# mpc57_clk.net
KiCad netlist of a schematic drawn in Altium Designer
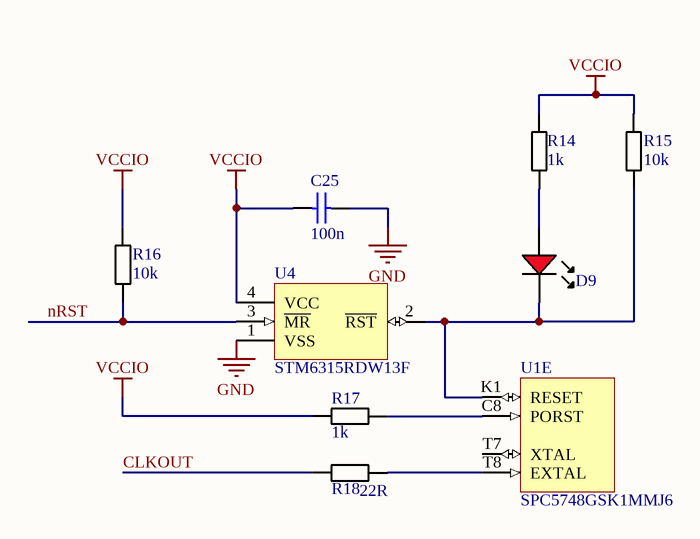
[diagram p0: mpc57_clk.SchDoc]

(export (version "E")
  (design (tool "Eeschema 10.0.6"))
  (components
    (comp (ref "C25")
      (value "100n")
      (footprint "CAPC0402_M")
      (description "100n, 0402")
      (fields (field (name "PART NUMBER") "CCHIP-100n-0402"))
      (libsource (lib "NewAE_AltiumLib") (part "CAP"))
    )
    (comp (ref "D9")
      (value "LED, 0603, Red")
      (footprint "LED-0603-RED")
      (description "Chip LED, Red")
      (fields (field (name "PART NUMBER") "LEDCHIP_0603_RED"))
      (libsource (lib "NewAE_AltiumLib") (part "LED_RED"))
    )
    (comp (ref "R14")
      (value "1k")
      (footprint "RESC1608X55N")
      (description "1k res, 0603, 1%, 1/10W")
      (fields (field (name "PART NUMBER") "RCHIP-1K-0603") (field (name "TOLERANCE") "1%"))
      (libsource (lib "NewAE_AltiumLib") (part "RES-EU"))
    )
    (comp (ref "R15")
      (value "10k")
      (footprint "RESC1608X55N")
      (description "10k res, 0603, 1%, 1/10W")
      (fields (field (name "PART NUMBER") "RCHIP-10K-0603") (field (name "TOLERANCE") "1%"))
      (libsource (lib "NewAE_AltiumLib") (part "RES-EU"))
    )
    (comp (ref "R16")
      (value "10k")
      (footprint "RESC1608X55N")
      (description "10k res, 0603, 1%, 1/10W")
      (fields (field (name "PART NUMBER") "RCHIP-10K-0603") (field (name "TOLERANCE") "1%"))
      (libsource (lib "NewAE_AltiumLib") (part "RES-EU"))
    )
    (comp (ref "R17")
      (value "1k")
      (footprint "RESC1608X55N")
      (description "1k res, 0603, 1%, 1/10W")
      (fields (field (name "PART NUMBER") "RCHIP-1K-0603") (field (name "TOLERANCE") "1%"))
      (libsource (lib "") (part "RES-EU_1"))
    )
    (comp (ref "R18")
      (value "22R")
      (footprint "RESC1608X55N")
      (description "22R res, 0603, 1%, 1/10W")
      (fields (field (name "PART NUMBER") "RCHIP-22R-0603") (field (name "TOLERANCE") "1%"))
      (libsource (lib "") (part "RES-EU_1"))
    )
    (comp (ref "U1")
      (value "SPC5748GSK1MMJ6")
      (footprint "NewAE_AltiumLib:BGA256C100P16X16_1700X1700X170")
      (description "Freescale 32-bit MCU, Triple core, 6MB Flash, 160MHz, -40/+125degC, Automotive Qualified, BGA 256")
      (libsource (lib "NewAE_AltiumLib") (part "SPC5748GSK1MMJ6"))
    )
    (comp (ref "U4")
      (value "STM6315RDW13F")
      (footprint "SOT143B")
      (description "2.93V Reset Controller, 112mS")
      (libsource (lib "NewAE_AltiumLib") (part "STM6315"))
    )
  )
  (nets
    (net (code "1") (name "/CLKOUT") (class "Default")
      (node (ref "R18") (pin "1") (pinfunction "1_1") (pintype "passive"))
    )
    (net (code "2") (name "/nRST") (class "Default")
      (node (ref "R16") (pin "2") (pinfunction "2_2") (pintype "passive"))
      (node (ref "U4") (pin "3") (pinfunction "~{MR}_3") (pintype "input"))
    )
    (net (code "3") (name "GND") (class "Default")
      (node (ref "C25") (pin "2") (pinfunction "2_2") (pintype "passive"))
      (node (ref "U4") (pin "1") (pinfunction "VSS_1") (pintype "power_in"))
    )
    (net (code "4") (name "Net-(D9-PadA)") (class "Default")
      (node (ref "D9") (pin "A") (pinfunction "A_A") (pintype "passive"))
      (node (ref "R14") (pin "2") (pinfunction "2_2") (pintype "passive"))
    )
    (net (code "5") (name "Net-(U1E-EXTAL)") (class "Default")
      (node (ref "R18") (pin "2") (pinfunction "2_2") (pintype "passive"))
      (node (ref "U1") (pin "T8") (pinfunction "EXTAL_T8") (pintype "input"))
    )
    (net (code "6") (name "Net-(U1E-PORST)") (class "Default")
      (node (ref "R17") (pin "2") (pinfunction "2_2") (pintype "passive"))
      (node (ref "U1") (pin "C8") (pinfunction "PORST_C8") (pintype "input"))
    )
    (net (code "7") (name "Net-(U1E-RESET)") (class "Default")
      (node (ref "D9") (pin "K") (pinfunction "K_K") (pintype "passive"))
      (node (ref "R15") (pin "2") (pinfunction "2_2") (pintype "passive"))
      (node (ref "U1") (pin "K1") (pinfunction "RESET_K1") (pintype "bidirectional"))
      (node (ref "U4") (pin "2") (pinfunction "~{RST}_2") (pintype "bidirectional"))
    )
    (net (code "8") (name "VCCIO") (class "Default")
      (node (ref "C25") (pin "1") (pinfunction "1_1") (pintype "passive"))
      (node (ref "R14") (pin "1") (pinfunction "1_1") (pintype "passive"))
      (node (ref "R15") (pin "1") (pinfunction "1_1") (pintype "passive"))
      (node (ref "R16") (pin "1") (pinfunction "1_1") (pintype "passive"))
      (node (ref "R17") (pin "1") (pinfunction "1_1") (pintype "passive"))
      (node (ref "U4") (pin "4") (pinfunction "VCC_4") (pintype "power_in"))
    )
    (net (code "9") (name "unconnected-(U1E-XTAL-PadT7)") (class "Default")
      (node (ref "U1") (pin "T7") (pinfunction "XTAL_T7") (pintype "bidirectional"))
    )
  )
)
